# stepper1.net
KiCad netlist of a schematic drawn in Altium Designer
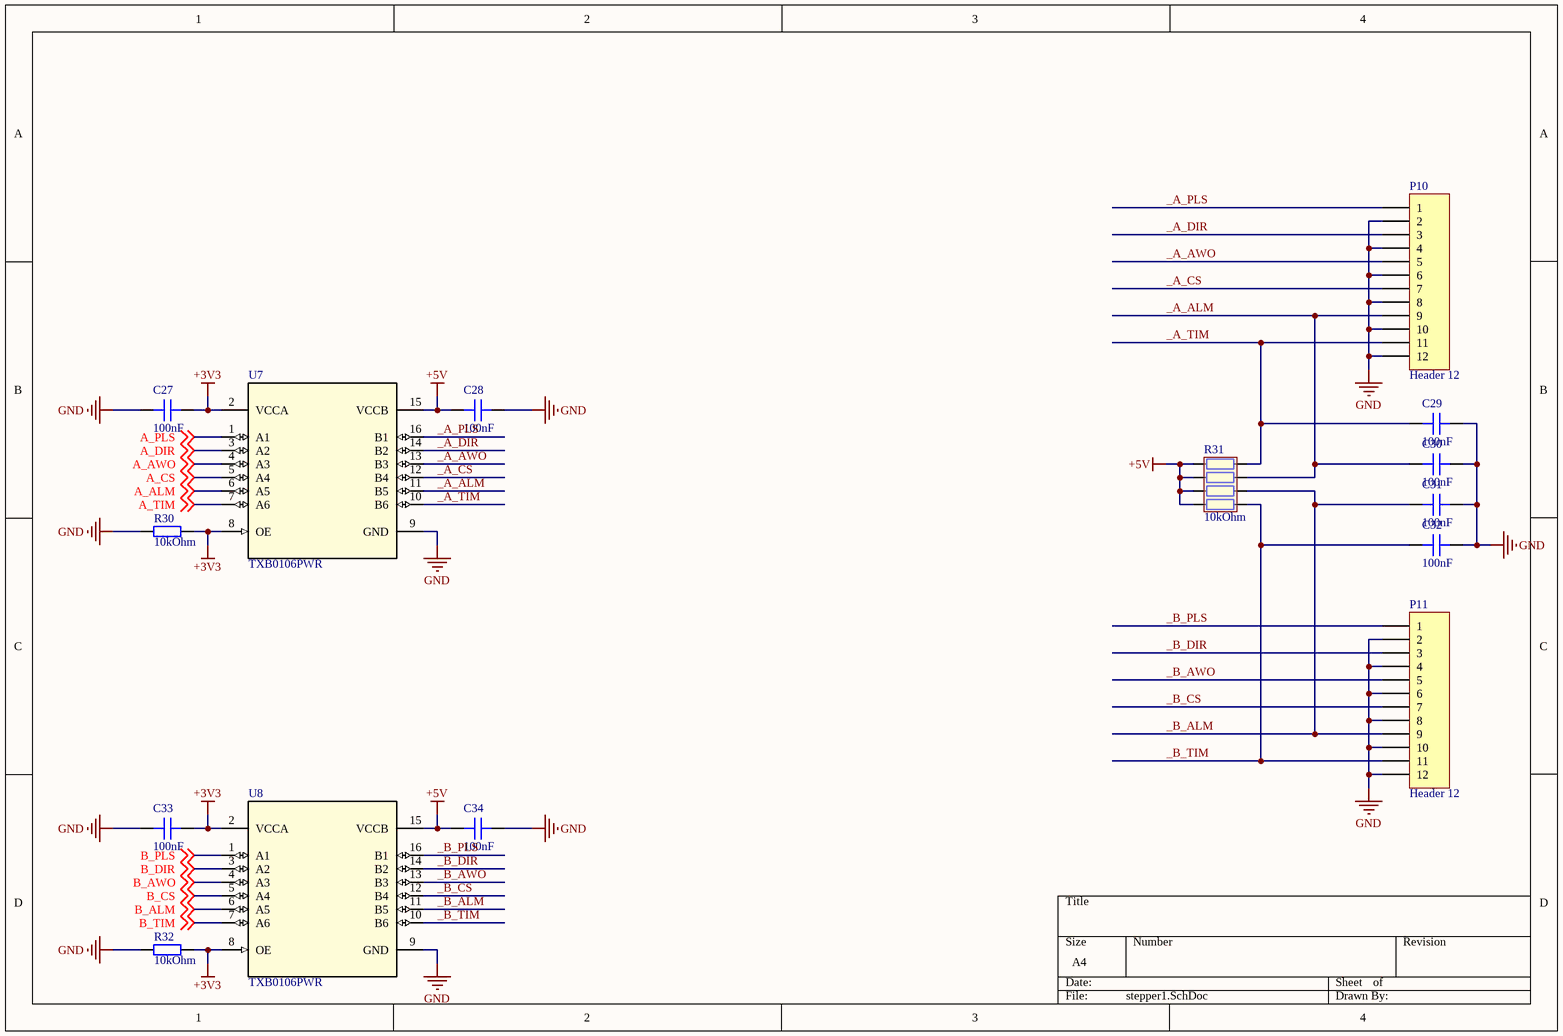
[diagram p0: stepper1.SchDoc]

(export (version "E")
  (design (tool "Eeschema 10.0.6"))
  (components
    (comp (ref "C27")
      (value "100nF")
      (footprint "CAPC2012-0805")
      (description "Capacitor")
      (fields (field (name "Comment") "Non-polar capacitor") (field (name "PUBLISHER") "Altium Limited"))
      (libsource (lib "MiLib") (part "Cap"))
    )
    (comp (ref "C28")
      (value "100nF")
      (footprint "CAPC2012-0805")
      (description "Capacitor")
      (fields (field (name "Comment") "Non-polar capacitor") (field (name "PUBLISHER") "Altium Limited"))
      (libsource (lib "MiLib") (part "Cap"))
    )
    (comp (ref "C29")
      (value "100nF")
      (footprint "CAPC2012-0805")
      (description "Capacitor")
      (fields (field (name "Comment") "Non-polar capacitor") (field (name "PUBLISHER") "Altium Limited"))
      (libsource (lib "MiLib") (part "Cap"))
    )
    (comp (ref "C30")
      (value "100nF")
      (footprint "CAPC2012-0805")
      (description "Capacitor")
      (fields (field (name "Comment") "Non-polar capacitor") (field (name "PUBLISHER") "Altium Limited"))
      (libsource (lib "MiLib") (part "Cap"))
    )
    (comp (ref "C31")
      (value "100nF")
      (footprint "CAPC2012-0805")
      (description "Capacitor")
      (fields (field (name "Comment") "Non-polar capacitor") (field (name "PUBLISHER") "Altium Limited"))
      (libsource (lib "MiLib") (part "Cap"))
    )
    (comp (ref "C32")
      (value "100nF")
      (footprint "CAPC2012-0805")
      (description "Capacitor")
      (fields (field (name "Comment") "Non-polar capacitor") (field (name "PUBLISHER") "Altium Limited"))
      (libsource (lib "MiLib") (part "Cap"))
    )
    (comp (ref "C33")
      (value "100nF")
      (footprint "CAPC2012-0805")
      (description "Capacitor")
      (fields (field (name "Comment") "Non-polar capacitor") (field (name "PUBLISHER") "Altium Limited"))
      (libsource (lib "MiLib") (part "Cap"))
    )
    (comp (ref "C34")
      (value "100nF")
      (footprint "CAPC2012-0805")
      (description "Capacitor")
      (fields (field (name "Comment") "Non-polar capacitor") (field (name "PUBLISHER") "Altium Limited"))
      (libsource (lib "MiLib") (part "Cap"))
    )
    (comp (ref "P10")
      (value "Header 12")
      (footprint "MOLEX 53426-1210")
      (description "Header, 12-Pin")
      (fields (field (name "PUBLISHER") "Altium Limited"))
      (libsource (lib "MiLib") (part "Header 12"))
    )
    (comp (ref "P11")
      (value "Header 12")
      (footprint "MOLEX 53426-1210")
      (description "Header, 12-Pin")
      (fields (field (name "PUBLISHER") "Altium Limited"))
      (libsource (lib "MiLib") (part "Header 12"))
    )
    (comp (ref "R30")
      (value "10kOhm")
      (footprint "RESC2012-0805")
      (description "Resistor")
      (fields (field (name "PUBLISHER") "Altium Limited"))
      (libsource (lib "MiLib") (part "Res"))
    )
    (comp (ref "R31")
      (value "10kOhm")
      (footprint "RES 0603 4PACK")
      (libsource (lib "MiLib") (part "Res 4Pack"))
    )
    (comp (ref "R32")
      (value "10kOhm")
      (footprint "RESC2012-0805")
      (description "Resistor")
      (fields (field (name "PUBLISHER") "Altium Limited"))
      (libsource (lib "MiLib") (part "Res"))
    )
    (comp (ref "U7")
      (value "TXB0106PWR")
      (footprint "TSSOP-16")
      (description "No Description Available")
      (fields
        (field (name "MANUFACTURER") "Texas Instruments")
        (field (name "COPYRIGHT") "Copyright (C) 2021 Accelerated Designs. All rights reserved")
      )
      (libsource (lib "misc") (part "TXB0106PWR"))
    )
    (comp (ref "U8")
      (value "TXB0106PWR")
      (footprint "TSSOP-16")
      (description "No Description Available")
      (fields
        (field (name "MANUFACTURER") "Texas Instruments")
        (field (name "COPYRIGHT") "Copyright (C) 2021 Accelerated Designs. All rights reserved")
      )
      (libsource (lib "misc") (part "TXB0106PWR"))
    )
  )
  (nets
    (net (code "1") (name "+3V3") (class "Default")
      (node (ref "C27") (pin "2") (pinfunction "2_2") (pintype "passive"))
      (node (ref "C33") (pin "2") (pinfunction "2_2") (pintype "passive"))
      (node (ref "R30") (pin "1") (pinfunction "1_1") (pintype "passive"))
      (node (ref "R32") (pin "1") (pinfunction "1_1") (pintype "passive"))
      (node (ref "U7") (pin "2") (pinfunction "VCCA_2") (pintype "power_in"))
      (node (ref "U7") (pin "8") (pinfunction "OE_8") (pintype "input"))
      (node (ref "U8") (pin "2") (pinfunction "VCCA_2") (pintype "power_in"))
      (node (ref "U8") (pin "8") (pinfunction "OE_8") (pintype "input"))
    )
    (net (code "2") (name "+5V") (class "Default")
      (node (ref "C28") (pin "1") (pinfunction "1_1") (pintype "passive"))
      (node (ref "C34") (pin "1") (pinfunction "1_1") (pintype "passive"))
      (node (ref "R31") (pin "1") (pinfunction "1_1") (pintype "passive"))
      (node (ref "R31") (pin "2") (pinfunction "2_2") (pintype "passive"))
      (node (ref "R31") (pin "3") (pinfunction "3_3") (pintype "passive"))
      (node (ref "R31") (pin "4") (pinfunction "4_4") (pintype "passive"))
      (node (ref "U7") (pin "15") (pinfunction "VCCB_15") (pintype "power_in"))
      (node (ref "U8") (pin "15") (pinfunction "VCCB_15") (pintype "power_in"))
    )
    (net (code "3") (name "/_A_ALM") (class "Default")
      (node (ref "C30") (pin "1") (pinfunction "1_1") (pintype "passive"))
      (node (ref "P10") (pin "9") (pinfunction "9_9") (pintype "passive"))
      (node (ref "R31") (pin "7") (pinfunction "7_7") (pintype "passive"))
      (node (ref "U7") (pin "11") (pinfunction "B5_11") (pintype "bidirectional"))
    )
    (net (code "4") (name "/_A_AWO") (class "Default")
      (node (ref "P10") (pin "5") (pinfunction "5_5") (pintype "passive"))
      (node (ref "U7") (pin "13") (pinfunction "B3_13") (pintype "bidirectional"))
    )
    (net (code "5") (name "/_A_CS") (class "Default")
      (node (ref "P10") (pin "7") (pinfunction "7_7") (pintype "passive"))
      (node (ref "U7") (pin "12") (pinfunction "B4_12") (pintype "bidirectional"))
    )
    (net (code "6") (name "/_A_DIR") (class "Default")
      (node (ref "P10") (pin "3") (pinfunction "3_3") (pintype "passive"))
      (node (ref "U7") (pin "14") (pinfunction "B2_14") (pintype "bidirectional"))
    )
    (net (code "7") (name "/_A_PLS") (class "Default")
      (node (ref "P10") (pin "1") (pinfunction "1_1") (pintype "passive"))
      (node (ref "U7") (pin "16") (pinfunction "B1_16") (pintype "bidirectional"))
    )
    (net (code "8") (name "/_A_TIM") (class "Default")
      (node (ref "C29") (pin "1") (pinfunction "1_1") (pintype "passive"))
      (node (ref "P10") (pin "11") (pinfunction "11_11") (pintype "passive"))
      (node (ref "R31") (pin "8") (pinfunction "8_8") (pintype "passive"))
      (node (ref "U7") (pin "10") (pinfunction "B6_10") (pintype "bidirectional"))
    )
    (net (code "9") (name "/_B_ALM") (class "Default")
      (node (ref "C31") (pin "1") (pinfunction "1_1") (pintype "passive"))
      (node (ref "P11") (pin "9") (pinfunction "9_9") (pintype "passive"))
      (node (ref "R31") (pin "6") (pinfunction "6_6") (pintype "passive"))
      (node (ref "U8") (pin "11") (pinfunction "B5_11") (pintype "bidirectional"))
    )
    (net (code "10") (name "/_B_AWO") (class "Default")
      (node (ref "P11") (pin "5") (pinfunction "5_5") (pintype "passive"))
      (node (ref "U8") (pin "13") (pinfunction "B3_13") (pintype "bidirectional"))
    )
    (net (code "11") (name "/_B_CS") (class "Default")
      (node (ref "P11") (pin "7") (pinfunction "7_7") (pintype "passive"))
      (node (ref "U8") (pin "12") (pinfunction "B4_12") (pintype "bidirectional"))
    )
    (net (code "12") (name "/_B_DIR") (class "Default")
      (node (ref "P11") (pin "3") (pinfunction "3_3") (pintype "passive"))
      (node (ref "U8") (pin "14") (pinfunction "B2_14") (pintype "bidirectional"))
    )
    (net (code "13") (name "/_B_PLS") (class "Default")
      (node (ref "P11") (pin "1") (pinfunction "1_1") (pintype "passive"))
      (node (ref "U8") (pin "16") (pinfunction "B1_16") (pintype "bidirectional"))
    )
    (net (code "14") (name "/_B_TIM") (class "Default")
      (node (ref "C32") (pin "1") (pinfunction "1_1") (pintype "passive"))
      (node (ref "P11") (pin "11") (pinfunction "11_11") (pintype "passive"))
      (node (ref "R31") (pin "5") (pinfunction "5_5") (pintype "passive"))
      (node (ref "U8") (pin "10") (pinfunction "B6_10") (pintype "bidirectional"))
    )
    (net (code "15") (name "A_ALM") (class "Default")
      (node (ref "U7") (pin "6") (pinfunction "A5_6") (pintype "bidirectional"))
    )
    (net (code "16") (name "A_AWO") (class "Default")
      (node (ref "U7") (pin "4") (pinfunction "A3_4") (pintype "bidirectional"))
    )
    (net (code "17") (name "A_CS") (class "Default")
      (node (ref "U7") (pin "5") (pinfunction "A4_5") (pintype "bidirectional"))
    )
    (net (code "18") (name "A_DIR") (class "Default")
      (node (ref "U7") (pin "3") (pinfunction "A2_3") (pintype "bidirectional"))
    )
    (net (code "19") (name "A_PLS") (class "Default")
      (node (ref "U7") (pin "1") (pinfunction "A1_1") (pintype "bidirectional"))
    )
    (net (code "20") (name "A_TIM") (class "Default")
      (node (ref "U7") (pin "7") (pinfunction "A6_7") (pintype "bidirectional"))
    )
    (net (code "21") (name "B_ALM") (class "Default")
      (node (ref "U8") (pin "6") (pinfunction "A5_6") (pintype "bidirectional"))
    )
    (net (code "22") (name "B_AWO") (class "Default")
      (node (ref "U8") (pin "4") (pinfunction "A3_4") (pintype "bidirectional"))
    )
    (net (code "23") (name "B_CS") (class "Default")
      (node (ref "U8") (pin "5") (pinfunction "A4_5") (pintype "bidirectional"))
    )
    (net (code "24") (name "B_DIR") (class "Default")
      (node (ref "U8") (pin "3") (pinfunction "A2_3") (pintype "bidirectional"))
    )
    (net (code "25") (name "B_PLS") (class "Default")
      (node (ref "U8") (pin "1") (pinfunction "A1_1") (pintype "bidirectional"))
    )
    (net (code "26") (name "B_TIM") (class "Default")
      (node (ref "U8") (pin "7") (pinfunction "A6_7") (pintype "bidirectional"))
    )
    (net (code "27") (name "GND") (class "Default")
      (node (ref "C27") (pin "1") (pinfunction "1_1") (pintype "passive"))
      (node (ref "C28") (pin "2") (pinfunction "2_2") (pintype "passive"))
      (node (ref "C29") (pin "2") (pinfunction "2_2") (pintype "passive"))
      (node (ref "C30") (pin "2") (pinfunction "2_2") (pintype "passive"))
      (node (ref "C31") (pin "2") (pinfunction "2_2") (pintype "passive"))
      (node (ref "C32") (pin "2") (pinfunction "2_2") (pintype "passive"))
      (node (ref "C33") (pin "1") (pinfunction "1_1") (pintype "passive"))
      (node (ref "C34") (pin "2") (pinfunction "2_2") (pintype "passive"))
      (node (ref "P10") (pin "10") (pinfunction "10_10") (pintype "passive"))
      (node (ref "P10") (pin "12") (pinfunction "12_12") (pintype "passive"))
      (node (ref "P10") (pin "2") (pinfunction "2_2") (pintype "passive"))
      (node (ref "P10") (pin "4") (pinfunction "4_4") (pintype "passive"))
      (node (ref "P10") (pin "6") (pinfunction "6_6") (pintype "passive"))
      (node (ref "P10") (pin "8") (pinfunction "8_8") (pintype "passive"))
      (node (ref "P11") (pin "10") (pinfunction "10_10") (pintype "passive"))
      (node (ref "P11") (pin "12") (pinfunction "12_12") (pintype "passive"))
      (node (ref "P11") (pin "2") (pinfunction "2_2") (pintype "passive"))
      (node (ref "P11") (pin "4") (pinfunction "4_4") (pintype "passive"))
      (node (ref "P11") (pin "6") (pinfunction "6_6") (pintype "passive"))
      (node (ref "P11") (pin "8") (pinfunction "8_8") (pintype "passive"))
      (node (ref "R30") (pin "2") (pinfunction "2_2") (pintype "passive"))
      (node (ref "R32") (pin "2") (pinfunction "2_2") (pintype "passive"))
      (node (ref "U7") (pin "9") (pinfunction "GND_9") (pintype "power_in"))
      (node (ref "U8") (pin "9") (pinfunction "GND_9") (pintype "power_in"))
    )
  )
)
